# EasyEDA_circuit_diagram.net
KiCad netlist of a schematic drawn in EasyEDA
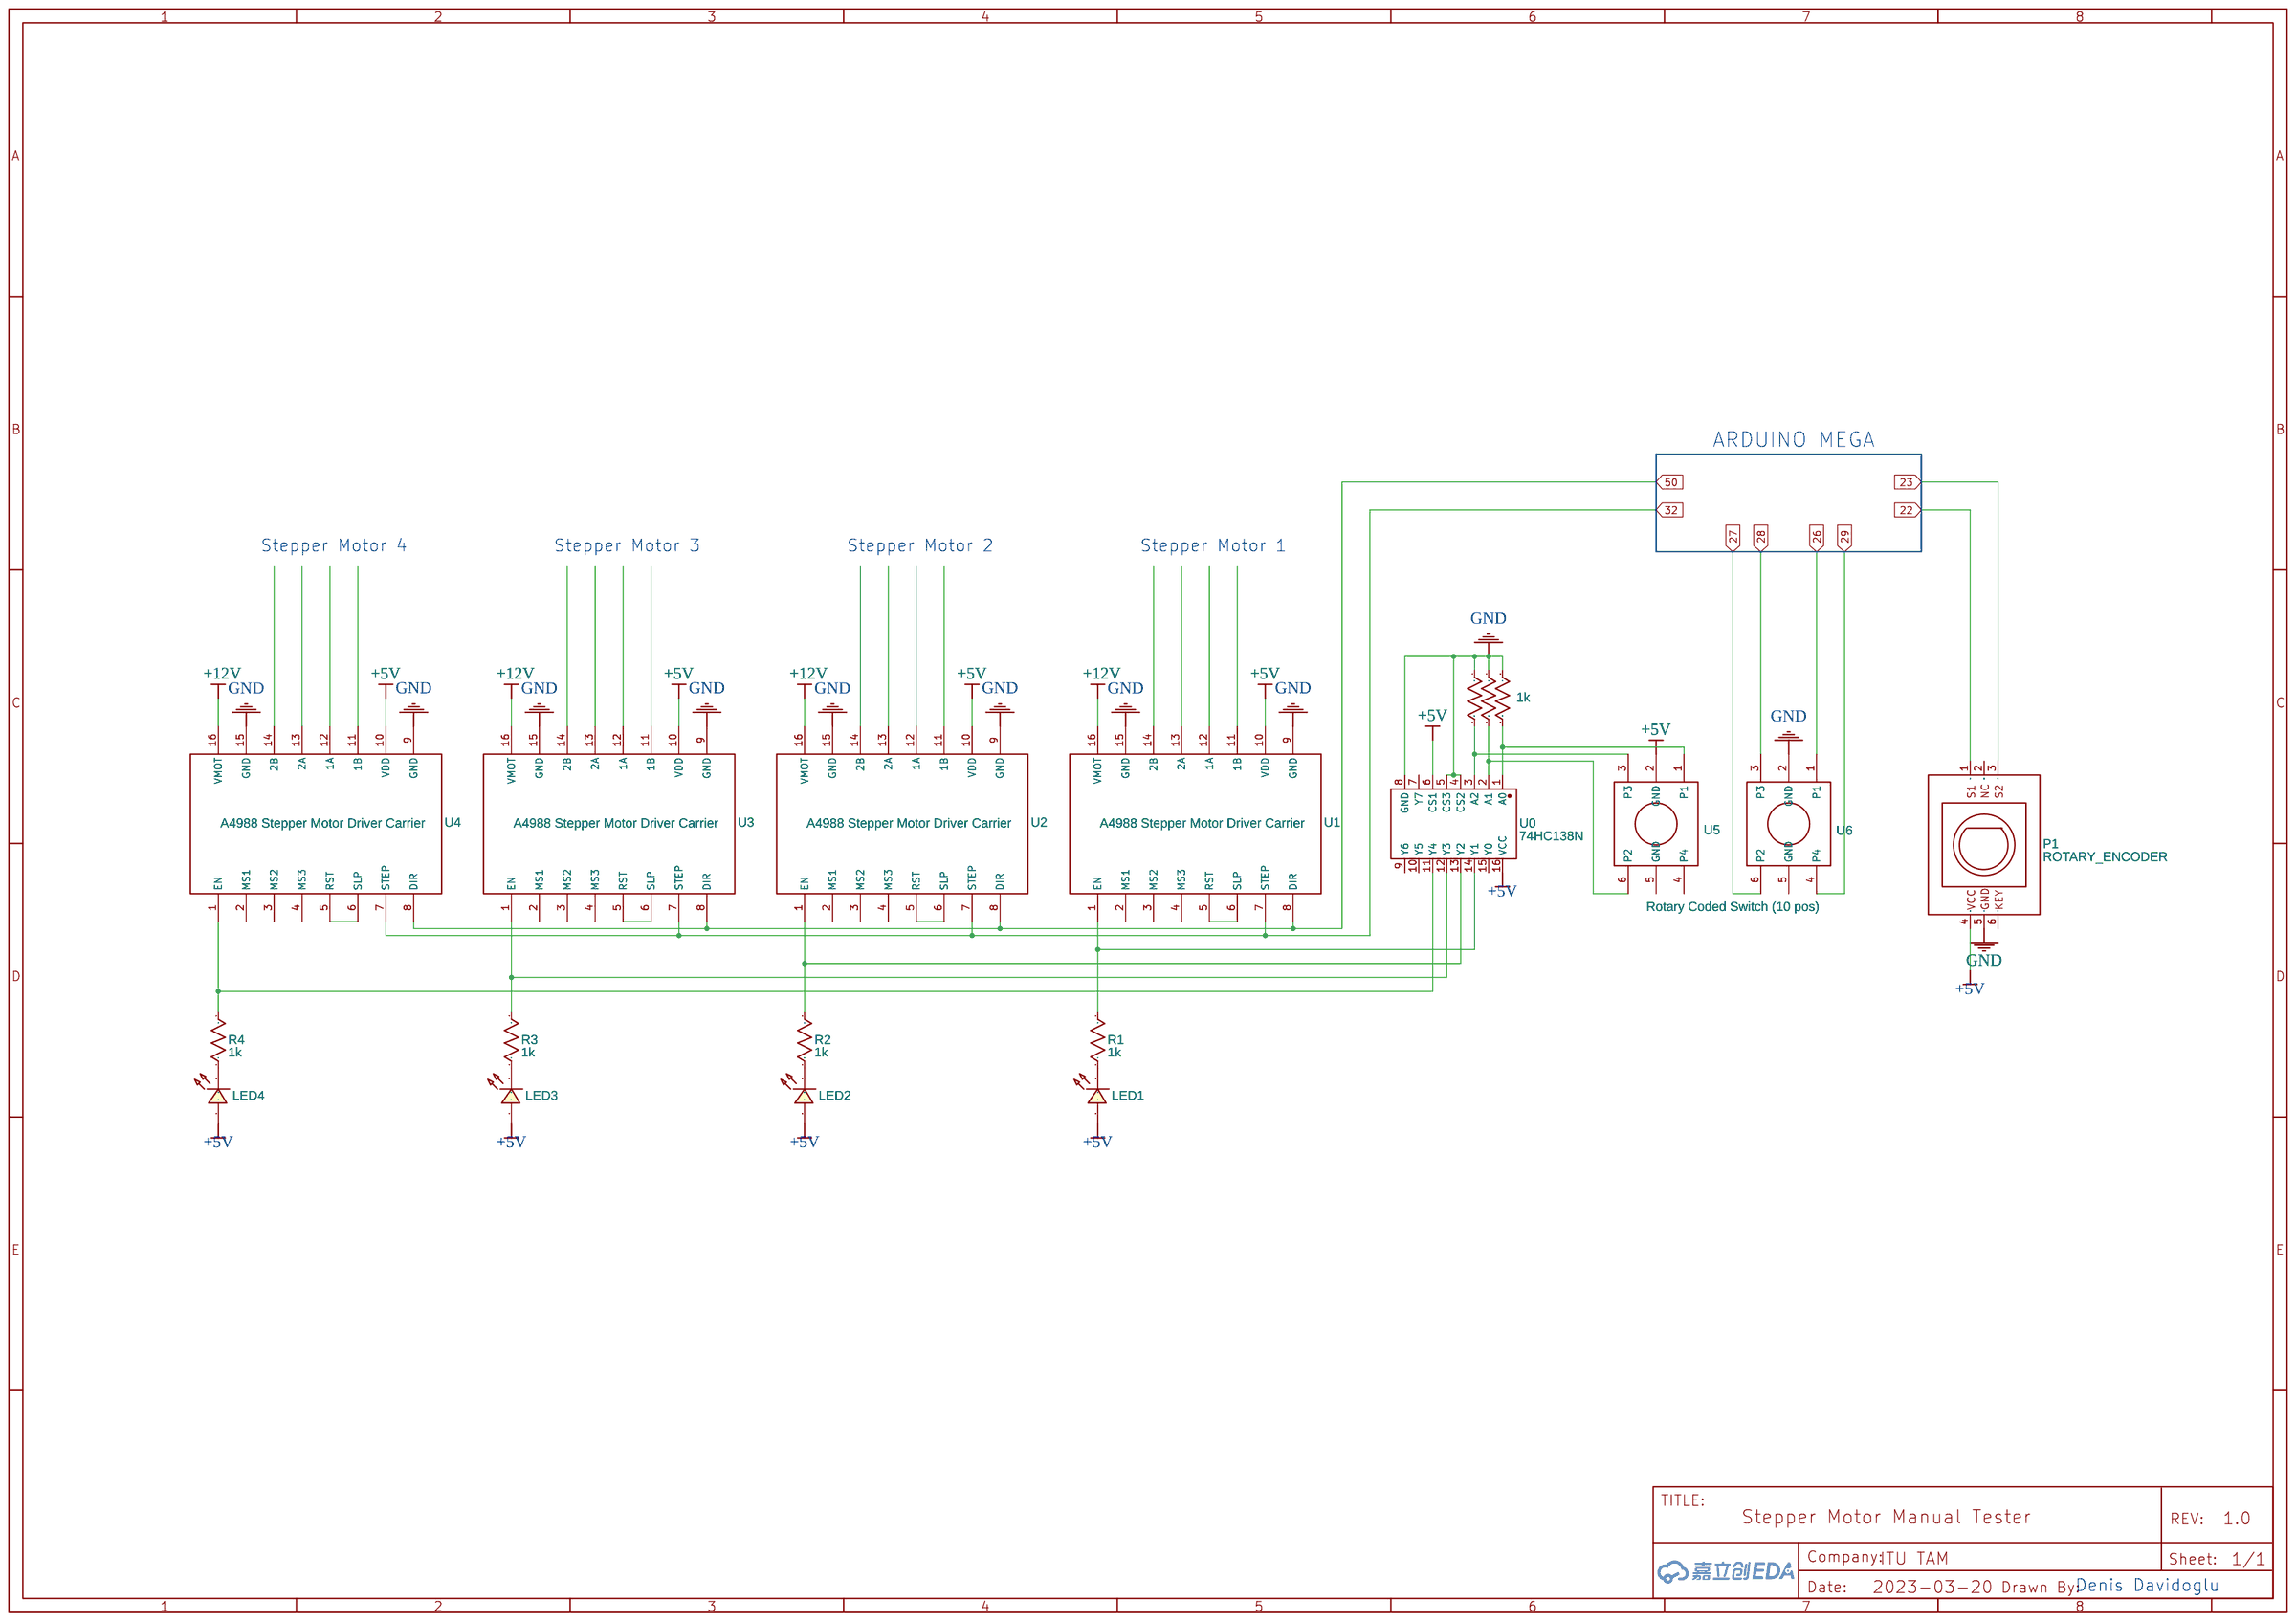
[diagram p0: schematic sheet]

(export (version "E")
  (design (tool "Eeschema 10.0.6"))
  (components
    (comp (ref "LED1")
      (value "LED-0603_R")
      (fields
        (field (name "BOM_Manufacturer Part") "19-217/R6C-AL1M2VY/3T")
        (field (name "BOM_Supplier Part") "C72044")
      )
      (libsource (lib "") (part "LED-0603_R"))
    )
    (comp (ref "LED2")
      (value "LED-0603_R")
      (fields
        (field (name "BOM_Manufacturer Part") "19-217/R6C-AL1M2VY/3T")
        (field (name "BOM_Supplier Part") "C72044")
      )
      (libsource (lib "") (part "LED-0603_R"))
    )
    (comp (ref "LED3")
      (value "LED-0603_R")
      (fields
        (field (name "BOM_Manufacturer Part") "19-217/R6C-AL1M2VY/3T")
        (field (name "BOM_Supplier Part") "C72044")
      )
      (libsource (lib "") (part "LED-0603_R"))
    )
    (comp (ref "LED4")
      (value "LED-0603_R")
      (fields
        (field (name "BOM_Manufacturer Part") "19-217/R6C-AL1M2VY/3T")
        (field (name "BOM_Supplier Part") "C72044")
      )
      (libsource (lib "") (part "LED-0603_R"))
    )
    (comp (ref "P1")
      (value "ROTARY_ENCODER")
      (fields (field (name "BOM_Manufacturer Part") "Female header/2.54mm2x3 Female header"))
      (libsource (lib "") (part "KY-040_ROTARY_ENCODER2_ZOS"))
    )
    (comp (ref "R1") (value "1k") (libsource (lib "") (part "R_0603_US")))
    (comp (ref "R2") (value "1k") (libsource (lib "") (part "R_0603_US")))
    (comp (ref "R3") (value "1k") (libsource (lib "") (part "R_0603_US")))
    (comp (ref "R4") (value "1k") (libsource (lib "") (part "R_0603_US")))
    (comp (ref "R5") (value "1k") (libsource (lib "") (part "R_0603_US_1")))
    (comp (ref "R6") (value "1k") (libsource (lib "") (part "R_0603_US_1")))
    (comp (ref "R7") (value "1k") (libsource (lib "") (part "R_0603_US_1")))
    (comp (ref "U0")
      (value "74HC138N")
      (fields (field (name "BOM_Supplier Part") "C507188"))
      (libsource (lib "") (part "74HC138N"))
    )
    (comp (ref "U1")
      (value "A4988 Stepper Motor Driver Carrier")
      (libsource (lib "") (part "A4988 Stepper Motor Driver Carrier"))
    )
    (comp (ref "U2")
      (value "A4988 Stepper Motor Driver Carrier")
      (libsource (lib "") (part "A4988 Stepper Motor Driver Carrier"))
    )
    (comp (ref "U3")
      (value "A4988 Stepper Motor Driver Carrier")
      (libsource (lib "") (part "A4988 Stepper Motor Driver Carrier"))
    )
    (comp (ref "U4")
      (value "A4988 Stepper Motor Driver Carrier")
      (libsource (lib "") (part "A4988 Stepper Motor Driver Carrier"))
    )
    (comp (ref "U5")
      (value "Rotary Coded Switch (10 pos)")
      (libsource (lib "") (part "Rotary Coded Switch (16 pos)"))
    )
    (comp (ref "U6")
      (value "Rotary Coded Switch (10 pos)")
      (libsource (lib "") (part "Rotary Coded Switch (16 pos)"))
    )
  )
  (nets
    (net (code "1") (name "+5V") (class "Default")
      (node (ref "LED1") (pin "1") (pinfunction "1_1") (pintype "unspecified"))
      (node (ref "LED2") (pin "1") (pinfunction "1_1") (pintype "unspecified"))
      (node (ref "LED3") (pin "1") (pinfunction "1_1") (pintype "unspecified"))
      (node (ref "LED4") (pin "1") (pinfunction "1_1") (pintype "unspecified"))
      (node (ref "P1") (pin "4") (pinfunction "GND_4") (pintype "unspecified"))
      (node (ref "U0") (pin "16") (pinfunction "VCC_16") (pintype "unspecified"))
      (node (ref "U0") (pin "6") (pinfunction "CS1_6") (pintype "unspecified"))
      (node (ref "U1") (pin "10") (pinfunction "VDD_10") (pintype "unspecified"))
      (node (ref "U2") (pin "10") (pinfunction "VDD_10") (pintype "unspecified"))
      (node (ref "U3") (pin "10") (pinfunction "VDD_10") (pintype "unspecified"))
      (node (ref "U4") (pin "10") (pinfunction "VDD_10") (pintype "unspecified"))
      (node (ref "U5") (pin "2") (pinfunction "GND_2") (pintype "passive"))
    )
    (net (code "2") (name "+12V") (class "Default")
      (node (ref "U1") (pin "16") (pinfunction "VMOT_16") (pintype "unspecified"))
      (node (ref "U2") (pin "16") (pinfunction "VMOT_16") (pintype "unspecified"))
      (node (ref "U3") (pin "16") (pinfunction "VMOT_16") (pintype "unspecified"))
      (node (ref "U4") (pin "16") (pinfunction "VMOT_16") (pintype "unspecified"))
    )
    (net (code "3") (name "22") (class "Default")
      (node (ref "P1") (pin "1") (pinfunction "GND_1") (pintype "unspecified"))
    )
    (net (code "4") (name "23") (class "Default")
      (node (ref "P1") (pin "3") (pinfunction "GND_3") (pintype "unspecified"))
    )
    (net (code "5") (name "26") (class "Default")
      (node (ref "U6") (pin "1") (pinfunction "P1_1") (pintype "output"))
    )
    (net (code "6") (name "27") (class "Default")
      (node (ref "U6") (pin "6") (pinfunction "P2_6") (pintype "output"))
    )
    (net (code "7") (name "28") (class "Default")
      (node (ref "U6") (pin "3") (pinfunction "P3_3") (pintype "output"))
    )
    (net (code "8") (name "29") (class "Default")
      (node (ref "U6") (pin "4") (pinfunction "P4_4") (pintype "output"))
    )
    (net (code "9") (name "32") (class "Default")
      (node (ref "U1") (pin "7") (pinfunction "STEP_7") (pintype "unspecified"))
      (node (ref "U2") (pin "7") (pinfunction "STEP_7") (pintype "unspecified"))
      (node (ref "U3") (pin "7") (pinfunction "STEP_7") (pintype "unspecified"))
      (node (ref "U4") (pin "7") (pinfunction "STEP_7") (pintype "unspecified"))
    )
    (net (code "10") (name "50") (class "Default")
      (node (ref "U1") (pin "8") (pinfunction "DIR_8") (pintype "unspecified"))
      (node (ref "U2") (pin "8") (pinfunction "DIR_8") (pintype "unspecified"))
      (node (ref "U3") (pin "8") (pinfunction "DIR_8") (pintype "unspecified"))
      (node (ref "U4") (pin "8") (pinfunction "DIR_8") (pintype "unspecified"))
    )
    (net (code "11") (name "GND") (class "Default")
      (node (ref "P1") (pin "5") (pinfunction "GND_5") (pintype "unspecified"))
      (node (ref "R5") (pin "1") (pinfunction "1_1") (pintype "unspecified"))
      (node (ref "R6") (pin "1") (pinfunction "1_1") (pintype "unspecified"))
      (node (ref "R7") (pin "1") (pinfunction "1_1") (pintype "unspecified"))
      (node (ref "U0") (pin "4") (pinfunction "CS2_4") (pintype "unspecified"))
      (node (ref "U0") (pin "5") (pinfunction "CS3_5") (pintype "unspecified"))
      (node (ref "U0") (pin "8") (pinfunction "GND_8") (pintype "unspecified"))
      (node (ref "U1") (pin "15") (pinfunction "GND_15") (pintype "unspecified"))
      (node (ref "U1") (pin "9") (pinfunction "GND_9") (pintype "unspecified"))
      (node (ref "U2") (pin "15") (pinfunction "GND_15") (pintype "unspecified"))
      (node (ref "U2") (pin "9") (pinfunction "GND_9") (pintype "unspecified"))
      (node (ref "U3") (pin "15") (pinfunction "GND_15") (pintype "unspecified"))
      (node (ref "U3") (pin "9") (pinfunction "GND_9") (pintype "unspecified"))
      (node (ref "U4") (pin "15") (pinfunction "GND_15") (pintype "unspecified"))
      (node (ref "U4") (pin "9") (pinfunction "GND_9") (pintype "unspecified"))
      (node (ref "U6") (pin "2") (pinfunction "GND_2") (pintype "passive"))
    )
    (net (code "12") (name "Net-(LED1-Pad2)") (class "Default")
      (node (ref "LED1") (pin "2") (pinfunction "2_2") (pintype "unspecified"))
      (node (ref "R1") (pin "1") (pinfunction "1_1") (pintype "unspecified"))
    )
    (net (code "13") (name "Net-(LED2-Pad2)") (class "Default")
      (node (ref "LED2") (pin "2") (pinfunction "2_2") (pintype "unspecified"))
      (node (ref "R2") (pin "1") (pinfunction "1_1") (pintype "unspecified"))
    )
    (net (code "14") (name "Net-(LED3-Pad2)") (class "Default")
      (node (ref "LED3") (pin "2") (pinfunction "2_2") (pintype "unspecified"))
      (node (ref "R3") (pin "1") (pinfunction "1_1") (pintype "unspecified"))
    )
    (net (code "15") (name "Net-(LED4-Pad2)") (class "Default")
      (node (ref "LED4") (pin "2") (pinfunction "2_2") (pintype "unspecified"))
      (node (ref "R4") (pin "1") (pinfunction "1_1") (pintype "unspecified"))
    )
    (net (code "16") (name "Net-(U0-A0)") (class "Default")
      (node (ref "R7") (pin "2") (pinfunction "2_2") (pintype "unspecified"))
      (node (ref "U0") (pin "1") (pinfunction "A0_1") (pintype "unspecified"))
      (node (ref "U5") (pin "1") (pinfunction "P1_1") (pintype "output"))
    )
    (net (code "17") (name "Net-(U0-A1)") (class "Default")
      (node (ref "R6") (pin "2") (pinfunction "2_2") (pintype "unspecified"))
      (node (ref "U0") (pin "2") (pinfunction "A1_2") (pintype "unspecified"))
      (node (ref "U5") (pin "6") (pinfunction "P2_6") (pintype "output"))
    )
    (net (code "18") (name "Net-(U0-A2)") (class "Default")
      (node (ref "R5") (pin "2") (pinfunction "2_2") (pintype "unspecified"))
      (node (ref "U0") (pin "3") (pinfunction "A2_3") (pintype "unspecified"))
      (node (ref "U5") (pin "3") (pinfunction "P3_3") (pintype "output"))
    )
    (net (code "19") (name "Net-(U0-Y1)") (class "Default")
      (node (ref "R1") (pin "2") (pinfunction "2_2") (pintype "unspecified"))
      (node (ref "U0") (pin "14") (pinfunction "Y1_14") (pintype "unspecified"))
      (node (ref "U1") (pin "1") (pinfunction "EN_1") (pintype "unspecified"))
    )
    (net (code "20") (name "Net-(U0-Y2)") (class "Default")
      (node (ref "R2") (pin "2") (pinfunction "2_2") (pintype "unspecified"))
      (node (ref "U0") (pin "13") (pinfunction "Y2_13") (pintype "unspecified"))
      (node (ref "U2") (pin "1") (pinfunction "EN_1") (pintype "unspecified"))
    )
    (net (code "21") (name "Net-(U0-Y3)") (class "Default")
      (node (ref "R3") (pin "2") (pinfunction "2_2") (pintype "unspecified"))
      (node (ref "U0") (pin "12") (pinfunction "Y3_12") (pintype "unspecified"))
      (node (ref "U3") (pin "1") (pinfunction "EN_1") (pintype "unspecified"))
    )
    (net (code "22") (name "Net-(U0-Y4)") (class "Default")
      (node (ref "R4") (pin "2") (pinfunction "2_2") (pintype "unspecified"))
      (node (ref "U0") (pin "11") (pinfunction "Y4_11") (pintype "unspecified"))
      (node (ref "U4") (pin "1") (pinfunction "EN_1") (pintype "unspecified"))
    )
    (net (code "23") (name "Net-(U1-RST)") (class "Default")
      (node (ref "U1") (pin "5") (pinfunction "RST_5") (pintype "unspecified"))
      (node (ref "U1") (pin "6") (pinfunction "SLP_6") (pintype "unspecified"))
    )
    (net (code "24") (name "Net-(U2-RST)") (class "Default")
      (node (ref "U2") (pin "5") (pinfunction "RST_5") (pintype "unspecified"))
      (node (ref "U2") (pin "6") (pinfunction "SLP_6") (pintype "unspecified"))
    )
    (net (code "25") (name "Net-(U3-RST)") (class "Default")
      (node (ref "U3") (pin "5") (pinfunction "RST_5") (pintype "unspecified"))
      (node (ref "U3") (pin "6") (pinfunction "SLP_6") (pintype "unspecified"))
    )
    (net (code "26") (name "Net-(U4-RST)") (class "Default")
      (node (ref "U4") (pin "5") (pinfunction "RST_5") (pintype "unspecified"))
      (node (ref "U4") (pin "6") (pinfunction "SLP_6") (pintype "unspecified"))
    )
    (net (code "27") (name "unconnected-(P1-GND-Pad2)") (class "Default")
      (node (ref "P1") (pin "2") (pinfunction "GND_2") (pintype "unspecified"))
    )
    (net (code "28") (name "unconnected-(P1-GND-Pad6)") (class "Default")
      (node (ref "P1") (pin "6") (pinfunction "GND_6") (pintype "unspecified"))
    )
    (net (code "29") (name "unconnected-(U0-Y0-Pad15)") (class "Default")
      (node (ref "U0") (pin "15") (pinfunction "Y0_15") (pintype "unspecified"))
    )
    (net (code "30") (name "unconnected-(U0-Y5-Pad10)") (class "Default")
      (node (ref "U0") (pin "10") (pinfunction "Y5_10") (pintype "unspecified"))
    )
    (net (code "31") (name "unconnected-(U0-Y6-Pad9)") (class "Default")
      (node (ref "U0") (pin "9") (pinfunction "Y6_9") (pintype "unspecified"))
    )
    (net (code "32") (name "unconnected-(U0-Y7-Pad7)") (class "Default")
      (node (ref "U0") (pin "7") (pinfunction "Y7_7") (pintype "unspecified"))
    )
    (net (code "33") (name "unconnected-(U1-1A-Pad12)") (class "Default")
      (node (ref "U1") (pin "12") (pinfunction "1A_12") (pintype "unspecified"))
    )
    (net (code "34") (name "unconnected-(U1-1B-Pad11)") (class "Default")
      (node (ref "U1") (pin "11") (pinfunction "1B_11") (pintype "unspecified"))
    )
    (net (code "35") (name "unconnected-(U1-2A-Pad13)") (class "Default")
      (node (ref "U1") (pin "13") (pinfunction "2A_13") (pintype "unspecified"))
    )
    (net (code "36") (name "unconnected-(U1-2B-Pad14)") (class "Default")
      (node (ref "U1") (pin "14") (pinfunction "2B_14") (pintype "unspecified"))
    )
    (net (code "37") (name "unconnected-(U1-MS1-Pad2)") (class "Default")
      (node (ref "U1") (pin "2") (pinfunction "MS1_2") (pintype "unspecified"))
    )
    (net (code "38") (name "unconnected-(U1-MS2-Pad3)") (class "Default")
      (node (ref "U1") (pin "3") (pinfunction "MS2_3") (pintype "unspecified"))
    )
    (net (code "39") (name "unconnected-(U1-MS3-Pad4)") (class "Default")
      (node (ref "U1") (pin "4") (pinfunction "MS3_4") (pintype "unspecified"))
    )
    (net (code "40") (name "unconnected-(U2-1A-Pad12)") (class "Default")
      (node (ref "U2") (pin "12") (pinfunction "1A_12") (pintype "unspecified"))
    )
    (net (code "41") (name "unconnected-(U2-1B-Pad11)") (class "Default")
      (node (ref "U2") (pin "11") (pinfunction "1B_11") (pintype "unspecified"))
    )
    (net (code "42") (name "unconnected-(U2-2A-Pad13)") (class "Default")
      (node (ref "U2") (pin "13") (pinfunction "2A_13") (pintype "unspecified"))
    )
    (net (code "43") (name "unconnected-(U2-2B-Pad14)") (class "Default")
      (node (ref "U2") (pin "14") (pinfunction "2B_14") (pintype "unspecified"))
    )
    (net (code "44") (name "unconnected-(U2-MS1-Pad2)") (class "Default")
      (node (ref "U2") (pin "2") (pinfunction "MS1_2") (pintype "unspecified"))
    )
    (net (code "45") (name "unconnected-(U2-MS2-Pad3)") (class "Default")
      (node (ref "U2") (pin "3") (pinfunction "MS2_3") (pintype "unspecified"))
    )
    (net (code "46") (name "unconnected-(U2-MS3-Pad4)") (class "Default")
      (node (ref "U2") (pin "4") (pinfunction "MS3_4") (pintype "unspecified"))
    )
    (net (code "47") (name "unconnected-(U3-1A-Pad12)") (class "Default")
      (node (ref "U3") (pin "12") (pinfunction "1A_12") (pintype "unspecified"))
    )
    (net (code "48") (name "unconnected-(U3-1B-Pad11)") (class "Default")
      (node (ref "U3") (pin "11") (pinfunction "1B_11") (pintype "unspecified"))
    )
    (net (code "49") (name "unconnected-(U3-2A-Pad13)") (class "Default")
      (node (ref "U3") (pin "13") (pinfunction "2A_13") (pintype "unspecified"))
    )
    (net (code "50") (name "unconnected-(U3-2B-Pad14)") (class "Default")
      (node (ref "U3") (pin "14") (pinfunction "2B_14") (pintype "unspecified"))
    )
    (net (code "51") (name "unconnected-(U3-MS1-Pad2)") (class "Default")
      (node (ref "U3") (pin "2") (pinfunction "MS1_2") (pintype "unspecified"))
    )
    (net (code "52") (name "unconnected-(U3-MS2-Pad3)") (class "Default")
      (node (ref "U3") (pin "3") (pinfunction "MS2_3") (pintype "unspecified"))
    )
    (net (code "53") (name "unconnected-(U3-MS3-Pad4)") (class "Default")
      (node (ref "U3") (pin "4") (pinfunction "MS3_4") (pintype "unspecified"))
    )
    (net (code "54") (name "unconnected-(U4-1A-Pad12)") (class "Default")
      (node (ref "U4") (pin "12") (pinfunction "1A_12") (pintype "unspecified"))
    )
    (net (code "55") (name "unconnected-(U4-1B-Pad11)") (class "Default")
      (node (ref "U4") (pin "11") (pinfunction "1B_11") (pintype "unspecified"))
    )
    (net (code "56") (name "unconnected-(U4-2A-Pad13)") (class "Default")
      (node (ref "U4") (pin "13") (pinfunction "2A_13") (pintype "unspecified"))
    )
    (net (code "57") (name "unconnected-(U4-2B-Pad14)") (class "Default")
      (node (ref "U4") (pin "14") (pinfunction "2B_14") (pintype "unspecified"))
    )
    (net (code "58") (name "unconnected-(U4-MS1-Pad2)") (class "Default")
      (node (ref "U4") (pin "2") (pinfunction "MS1_2") (pintype "unspecified"))
    )
    (net (code "59") (name "unconnected-(U4-MS2-Pad3)") (class "Default")
      (node (ref "U4") (pin "3") (pinfunction "MS2_3") (pintype "unspecified"))
    )
    (net (code "60") (name "unconnected-(U4-MS3-Pad4)") (class "Default")
      (node (ref "U4") (pin "4") (pinfunction "MS3_4") (pintype "unspecified"))
    )
    (net (code "61") (name "unconnected-(U5-GND-Pad5)") (class "Default")
      (node (ref "U5") (pin "5") (pinfunction "GND_5") (pintype "passive"))
    )
    (net (code "62") (name "unconnected-(U5-P4-Pad4)") (class "Default")
      (node (ref "U5") (pin "4") (pinfunction "P4_4") (pintype "output"))
    )
    (net (code "63") (name "unconnected-(U6-GND-Pad5)") (class "Default")
      (node (ref "U6") (pin "5") (pinfunction "GND_5") (pintype "passive"))
    )
  )
)
